# TK513_Limiter.net
KiCad netlist of a schematic drawn in Altium Designer
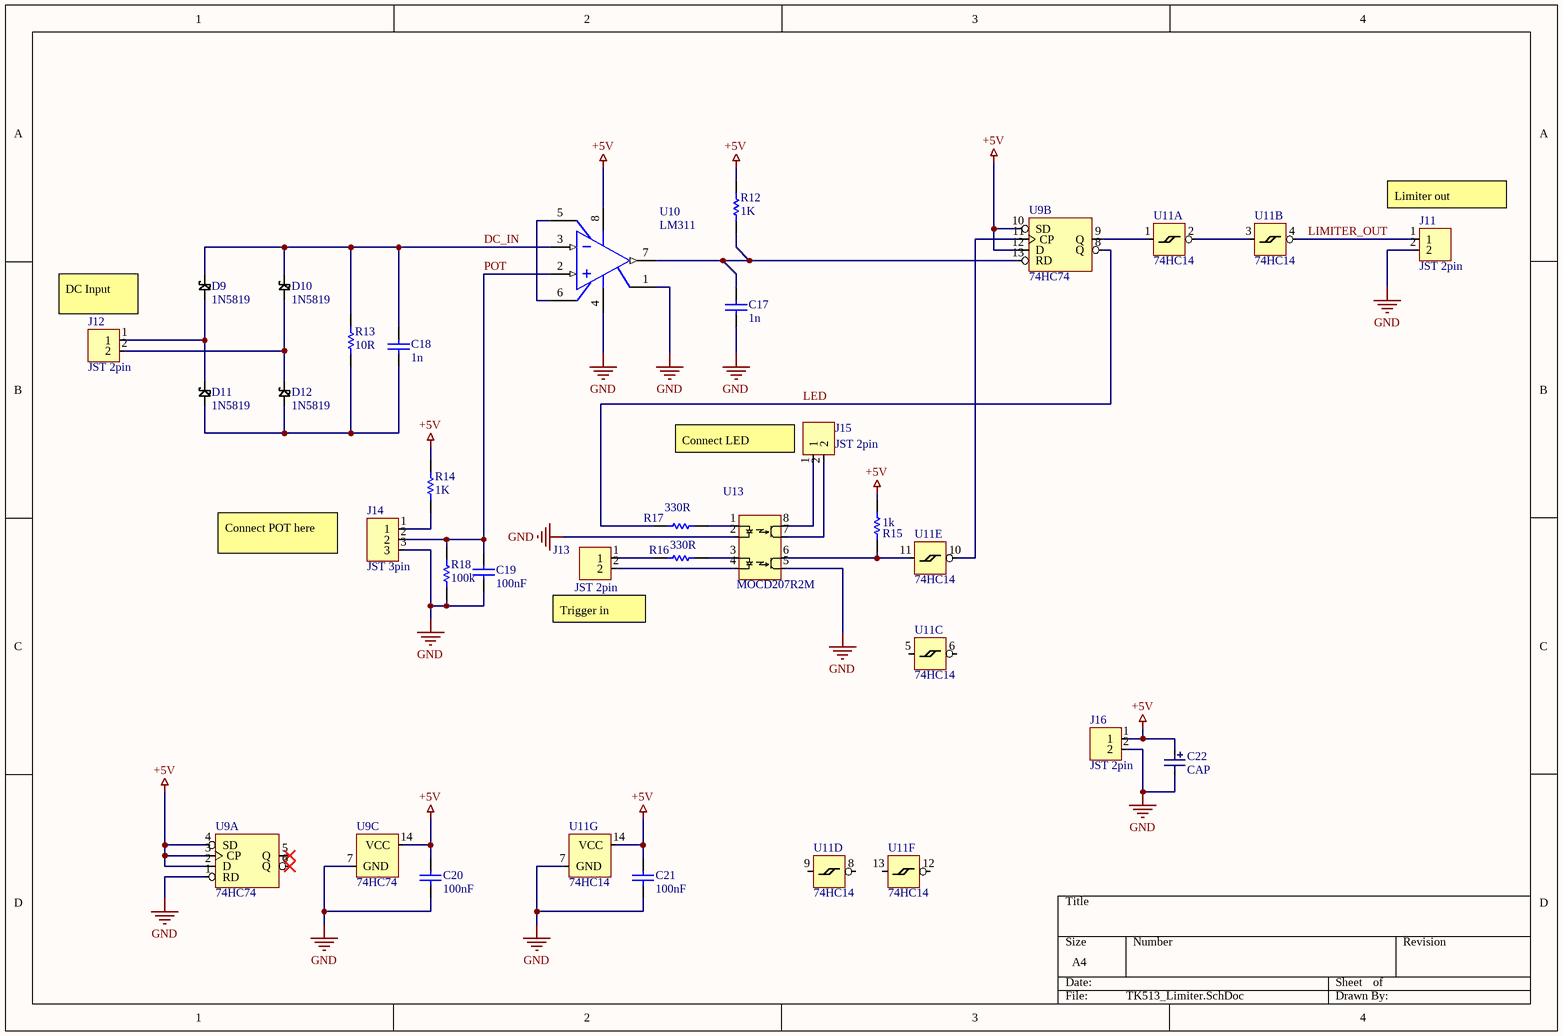
[diagram p0: TK513_Limiter.SchDoc]

(export (version "E")
  (design (tool "Eeschema 10.0.6"))
  (components
    (comp (ref "C17")
      (value "1n")
      (footprint "CAPC0805(2012)100_L")
      (description "CAP 100nF 50V ±5% 0805 (2012 Metric) Thickness 1mm SMD")
      (fields (field (name "TOLERANCE") "±5%"))
      (libsource (lib "Altium Content Vault") (part "CMP-1036-04418-1"))
    )
    (comp (ref "C18")
      (value "1n")
      (footprint "CAPC0805(2012)100_L")
      (description "CAP 100nF 50V ±5% 0805 (2012 Metric) Thickness 1mm SMD")
      (fields (field (name "TOLERANCE") "±5%"))
      (libsource (lib "Altium Content Vault") (part "CMP-1036-04418-1"))
    )
    (comp (ref "C19")
      (value "100nF")
      (footprint "CAPC0805(2012)100_L")
      (description "CAP 100nF 50V ±5% 0805 (2012 Metric) Thickness 1mm SMD")
      (fields (field (name "TOLERANCE") "±5%"))
      (libsource (lib "Altium Content Vault") (part "CMP-1036-04418-1"))
    )
    (comp (ref "C20")
      (value "100nF")
      (footprint "CAPC0805(2012)100_L")
      (description "CAP 100nF 50V ±5% 0805 (2012 Metric) Thickness 1mm SMD")
      (fields (field (name "TOLERANCE") "±5%"))
      (libsource (lib "Altium Content Vault") (part "CMP-1036-04418-1"))
    )
    (comp (ref "C21")
      (value "100nF")
      (footprint "CAPC0805(2012)100_L")
      (description "CAP 100nF 50V ±5% 0805 (2012 Metric) Thickness 1mm SMD")
      (fields (field (name "TOLERANCE") "±5%"))
      (libsource (lib "Altium Content Vault") (part "CMP-1036-04418-1"))
    )
    (comp (ref "C22") (value "CAP") (footprint "CAP 2.5mm") (libsource (lib "Schlib1") (part "CAP")))
    (comp (ref "D9") (value "1N5819") (footprint "1N5819") (libsource (lib "Schlib1") (part "1N5819")))
    (comp (ref "D10") (value "1N5819") (footprint "1N5819") (libsource (lib "Schlib1") (part "1N5819")))
    (comp (ref "D11") (value "1N5819") (footprint "1N5819") (libsource (lib "Schlib1") (part "1N5819")))
    (comp (ref "D12") (value "1N5819") (footprint "1N5819") (libsource (lib "Schlib1") (part "1N5819")))
    (comp (ref "J11") (value "JST 2pin") (footprint "JST 2pin") (libsource (lib "") (part "JST 2pin_2")))
    (comp (ref "J12") (value "JST 2pin") (footprint "JST 2pin") (libsource (lib "Schlib1") (part "JST 2pin")))
    (comp (ref "J13") (value "JST 2pin") (footprint "JST 2pin") (libsource (lib "Schlib1") (part "JST 2pin")))
    (comp (ref "J14") (value "JST 3pin") (footprint "JST 3pin") (libsource (lib "Schlib1") (part "JST 3pin")))
    (comp (ref "J15") (value "JST 2pin") (footprint "JST 2pin") (libsource (lib "") (part "JST 2pin_1")))
    (comp (ref "J16") (value "JST 2pin") (footprint "JST 2pin") (libsource (lib "Schlib1") (part "JST 2pin")))
    (comp (ref "R12")
      (value "1K")
      (footprint "RESC0805(2012)_L")
      (description "330R 0.125W 5% 0805 (2012 Metric)  SMD")
      (fields (field (name "TOLERANCE") "5 %") (field (name "POWER") "0.125 W"))
      (libsource (lib "Altium Content Vault") (part "CMP-1013-00062-1"))
    )
    (comp (ref "R13")
      (value "10R")
      (footprint "RESC0805(2012)_L")
      (description "330R 0.125W 5% 0805 (2012 Metric)  SMD")
      (fields (field (name "TOLERANCE") "5 %") (field (name "POWER") "0.125 W"))
      (libsource (lib "Altium Content Vault") (part "CMP-1013-00062-1"))
    )
    (comp (ref "R14")
      (value "1K")
      (footprint "RESC0805(2012)_L")
      (description "330R 0.125W 5% 0805 (2012 Metric)  SMD")
      (fields (field (name "TOLERANCE") "5 %") (field (name "POWER") "0.125 W"))
      (libsource (lib "Altium Content Vault") (part "CMP-1013-00062-1"))
    )
    (comp (ref "R15")
      (value "1k")
      (footprint "RESC0805(2012)_N")
      (description "1K 0.125W 5% 0805 (2012 Metric)  SMD")
      (fields (field (name "POWER") "0.125 W") (field (name "TOLERANCE") "5 %"))
      (libsource (lib "Altium Content Vault") (part "CMP-1013-00074-1"))
    )
    (comp (ref "R16")
      (value "330R")
      (footprint "RESC0805(2012)_L")
      (description "330R 0.125W 5% 0805 (2012 Metric)  SMD")
      (fields (field (name "TOLERANCE") "5 %") (field (name "POWER") "0.125 W"))
      (libsource (lib "Altium Content Vault") (part "CMP-1013-00062-1"))
    )
    (comp (ref "R17")
      (value "330R")
      (footprint "RESC0805(2012)_L")
      (description "330R 0.125W 5% 0805 (2012 Metric)  SMD")
      (fields (field (name "TOLERANCE") "5 %") (field (name "POWER") "0.125 W"))
      (libsource (lib "Altium Content Vault") (part "CMP-1013-00062-1"))
    )
    (comp (ref "R18")
      (value "100k")
      (footprint "RESC0805(2012)_L")
      (description "330R 0.125W 5% 0805 (2012 Metric)  SMD")
      (fields (field (name "TOLERANCE") "5 %") (field (name "POWER") "0.125 W"))
      (libsource (lib "Altium Content Vault") (part "CMP-1013-00062-1"))
    )
    (comp (ref "U9") (value "74HC74") (footprint "SOP14") (libsource (lib "Schlib1") (part "74HC74")))
    (comp (ref "U10") (value "LM311") (footprint "SOIC8-WIDE") (libsource (lib "Schlib1") (part "LM311")))
    (comp (ref "U11") (value "74HC14") (footprint "SOP14") (libsource (lib "Schlib1") (part "74HC14")))
    (comp (ref "U13") (value "MOCD207R2M") (footprint "SOP8") (libsource (lib "Schlib1") (part "MOCD207R2M")))
  )
  (nets
    (net (code "1") (name "+5V") (class "Default")
      (node (ref "C20") (pin "2") (pinfunction "2_2") (pintype "passive"))
      (node (ref "C21") (pin "2") (pinfunction "2_2") (pintype "passive"))
      (node (ref "C22") (pin "2") (pinfunction "2_2") (pintype "passive"))
      (node (ref "J16") (pin "1") (pinfunction "1_1") (pintype "passive"))
      (node (ref "R12") (pin "1") (pinfunction "1_1") (pintype "passive"))
      (node (ref "R14") (pin "1") (pinfunction "1_1") (pintype "passive"))
      (node (ref "R15") (pin "2") (pinfunction "2_2") (pintype "passive"))
      (node (ref "U10") (pin "8") (pinfunction "V+_8") (pintype "power_in"))
      (node (ref "U11") (pin "14") (pinfunction "VCC_14") (pintype "passive"))
      (node (ref "U9") (pin "10") (pinfunction "SD_10") (pintype "passive"))
      (node (ref "U9") (pin "12") (pinfunction "D_12") (pintype "passive"))
      (node (ref "U9") (pin "14") (pinfunction "VCC_14") (pintype "passive"))
      (node (ref "U9") (pin "2") (pinfunction "D_2") (pintype "passive"))
      (node (ref "U9") (pin "3") (pinfunction "CP_3") (pintype "passive"))
      (node (ref "U9") (pin "4") (pinfunction "SD_4") (pintype "passive"))
    )
    (net (code "2") (name "/DC_IN") (class "Default")
      (node (ref "C18") (pin "2") (pinfunction "2_2") (pintype "passive"))
      (node (ref "D10") (pin "K") (pinfunction "K_K") (pintype "passive"))
      (node (ref "D9") (pin "K") (pinfunction "K_K") (pintype "passive"))
      (node (ref "R13") (pin "1") (pinfunction "1_1") (pintype "passive"))
      (node (ref "U10") (pin "3") (pinfunction "IN-_3") (pintype "input"))
    )
    (net (code "3") (name "/LED") (class "Default")
      (node (ref "R17") (pin "2") (pinfunction "2_2") (pintype "passive"))
      (node (ref "U9") (pin "8") (pinfunction "Q_8") (pintype "passive"))
    )
    (net (code "4") (name "/LIMITER_OUT") (class "Default")
      (node (ref "J11") (pin "1") (pinfunction "1_1") (pintype "passive"))
      (node (ref "U11") (pin "4") (pinfunction "4_4") (pintype "passive"))
    )
    (net (code "5") (name "/POT") (class "Default")
      (node (ref "C19") (pin "2") (pinfunction "2_2") (pintype "passive"))
      (node (ref "J14") (pin "2") (pinfunction "2_2") (pintype "passive"))
      (node (ref "R18") (pin "1") (pinfunction "1_1") (pintype "passive"))
      (node (ref "U10") (pin "2") (pinfunction "IN+_2") (pintype "input"))
    )
    (net (code "6") (name "GND") (class "Default")
      (node (ref "C17") (pin "1") (pinfunction "1_1") (pintype "passive"))
      (node (ref "C19") (pin "1") (pinfunction "1_1") (pintype "passive"))
      (node (ref "C20") (pin "1") (pinfunction "1_1") (pintype "passive"))
      (node (ref "C21") (pin "1") (pinfunction "1_1") (pintype "passive"))
      (node (ref "C22") (pin "1") (pinfunction "1_1") (pintype "passive"))
      (node (ref "J11") (pin "2") (pinfunction "2_2") (pintype "passive"))
      (node (ref "J14") (pin "3") (pinfunction "3_3") (pintype "passive"))
      (node (ref "J16") (pin "2") (pinfunction "2_2") (pintype "passive"))
      (node (ref "R18") (pin "2") (pinfunction "2_2") (pintype "passive"))
      (node (ref "U10") (pin "1") (pinfunction "GND_1") (pintype "power_in"))
      (node (ref "U10") (pin "4") (pinfunction "V-_4") (pintype "power_in"))
      (node (ref "U11") (pin "7") (pinfunction "GND_7") (pintype "passive"))
      (node (ref "U13") (pin "2") (pinfunction "2_2") (pintype "passive"))
      (node (ref "U13") (pin "5") (pinfunction "5_5") (pintype "passive"))
      (node (ref "U9") (pin "1") (pinfunction "RD_1") (pintype "passive"))
      (node (ref "U9") (pin "7") (pinfunction "GND_7") (pintype "passive"))
    )
    (net (code "7") (name "Net-(C18-Pad1)") (class "Default")
      (node (ref "C18") (pin "1") (pinfunction "1_1") (pintype "passive"))
      (node (ref "D11") (pin "A") (pinfunction "A_A") (pintype "passive"))
      (node (ref "D12") (pin "A") (pinfunction "A_A") (pintype "passive"))
      (node (ref "R13") (pin "2") (pinfunction "2_2") (pintype "passive"))
    )
    (net (code "8") (name "Net-(D10-PadA)") (class "Default")
      (node (ref "D10") (pin "A") (pinfunction "A_A") (pintype "passive"))
      (node (ref "D12") (pin "K") (pinfunction "K_K") (pintype "passive"))
      (node (ref "J12") (pin "2") (pinfunction "2_2") (pintype "passive"))
    )
    (net (code "9") (name "Net-(D11-PadK)") (class "Default")
      (node (ref "D11") (pin "K") (pinfunction "K_K") (pintype "passive"))
      (node (ref "D9") (pin "A") (pinfunction "A_A") (pintype "passive"))
      (node (ref "J12") (pin "1") (pinfunction "1_1") (pintype "passive"))
    )
    (net (code "10") (name "Net-(J13-Pad1)") (class "Default")
      (node (ref "J13") (pin "1") (pinfunction "1_1") (pintype "passive"))
      (node (ref "R16") (pin "2") (pinfunction "2_2") (pintype "passive"))
    )
    (net (code "11") (name "Net-(J13-Pad2)") (class "Default")
      (node (ref "J13") (pin "2") (pinfunction "2_2") (pintype "passive"))
      (node (ref "U13") (pin "4") (pinfunction "4_4") (pintype "passive"))
    )
    (net (code "12") (name "Net-(J14-Pad1)") (class "Default")
      (node (ref "J14") (pin "1") (pinfunction "1_1") (pintype "passive"))
      (node (ref "R14") (pin "2") (pinfunction "2_2") (pintype "passive"))
    )
    (net (code "13") (name "Net-(J15-Pad1)") (class "Default")
      (node (ref "J15") (pin "1") (pinfunction "1_1") (pintype "passive"))
      (node (ref "U13") (pin "8") (pinfunction "8_8") (pintype "passive"))
    )
    (net (code "14") (name "Net-(J15-Pad2)") (class "Default")
      (node (ref "J15") (pin "2") (pinfunction "2_2") (pintype "passive"))
      (node (ref "U13") (pin "7") (pinfunction "7_7") (pintype "passive"))
    )
    (net (code "15") (name "Net-(R15-Pad1)") (class "Default")
      (node (ref "R15") (pin "1") (pinfunction "1_1") (pintype "passive"))
      (node (ref "U11") (pin "11") (pinfunction "11_11") (pintype "passive"))
      (node (ref "U13") (pin "6") (pinfunction "6_6") (pintype "passive"))
    )
    (net (code "16") (name "Net-(R16-Pad1)") (class "Default")
      (node (ref "R16") (pin "1") (pinfunction "1_1") (pintype "passive"))
      (node (ref "U13") (pin "3") (pinfunction "3_3") (pintype "passive"))
    )
    (net (code "17") (name "Net-(R17-Pad1)") (class "Default")
      (node (ref "R17") (pin "1") (pinfunction "1_1") (pintype "passive"))
      (node (ref "U13") (pin "1") (pinfunction "1_1") (pintype "passive"))
    )
    (net (code "18") (name "Net-(U9B-CP)") (class "Default")
      (node (ref "U11") (pin "10") (pinfunction "10_10") (pintype "passive"))
      (node (ref "U9") (pin "11") (pinfunction "CP_11") (pintype "passive"))
    )
    (net (code "19") (name "Net-(U10-BAL)") (class "Default")
      (node (ref "U10") (pin "5") (pinfunction "BAL_5") (pintype "passive"))
      (node (ref "U10") (pin "6") (pinfunction "BAL/STB_6") (pintype "passive"))
    )
    (net (code "20") (name "Net-(U10-OUT)") (class "Default")
      (node (ref "C17") (pin "2") (pinfunction "2_2") (pintype "passive"))
      (node (ref "R12") (pin "2") (pinfunction "2_2") (pintype "passive"))
      (node (ref "U10") (pin "7") (pinfunction "OUT_7") (pintype "output"))
      (node (ref "U9") (pin "13") (pinfunction "RD_13") (pintype "passive"))
    )
    (net (code "21") (name "Net-(U11-Pad1)") (class "Default")
      (node (ref "U11") (pin "1") (pinfunction "1_1") (pintype "passive"))
      (node (ref "U9") (pin "9") (pinfunction "Q_9") (pintype "passive"))
    )
    (net (code "22") (name "Net-(U11-Pad2)") (class "Default")
      (node (ref "U11") (pin "2") (pinfunction "2_2") (pintype "passive"))
      (node (ref "U11") (pin "3") (pinfunction "3_3") (pintype "passive"))
    )
    (net (code "23") (name "unconnected-(U9A-Q-Pad5)") (class "Default")
      (node (ref "U9") (pin "5") (pinfunction "Q_5") (pintype "passive+no_connect"))
    )
    (net (code "24") (name "unconnected-(U9A-Q-Pad6)") (class "Default")
      (node (ref "U9") (pin "6") (pinfunction "Q_6") (pintype "passive+no_connect"))
    )
    (net (code "25") (name "unconnected-(U11-Pad5)") (class "Default")
      (node (ref "U11") (pin "5") (pinfunction "5_5") (pintype "passive"))
    )
    (net (code "26") (name "unconnected-(U11-Pad6)") (class "Default")
      (node (ref "U11") (pin "6") (pinfunction "6_6") (pintype "passive"))
    )
    (net (code "27") (name "unconnected-(U11-Pad8)") (class "Default")
      (node (ref "U11") (pin "8") (pinfunction "8_8") (pintype "passive"))
    )
    (net (code "28") (name "unconnected-(U11-Pad9)") (class "Default")
      (node (ref "U11") (pin "9") (pinfunction "9_9") (pintype "passive"))
    )
    (net (code "29") (name "unconnected-(U11-Pad12)") (class "Default")
      (node (ref "U11") (pin "12") (pinfunction "12_12") (pintype "passive"))
    )
    (net (code "30") (name "unconnected-(U11-Pad13)") (class "Default")
      (node (ref "U11") (pin "13") (pinfunction "13_13") (pintype "passive"))
    )
  )
)
